# STM32_microcontroller_power.net
KiCad netlist of a schematic drawn in Altium Designer
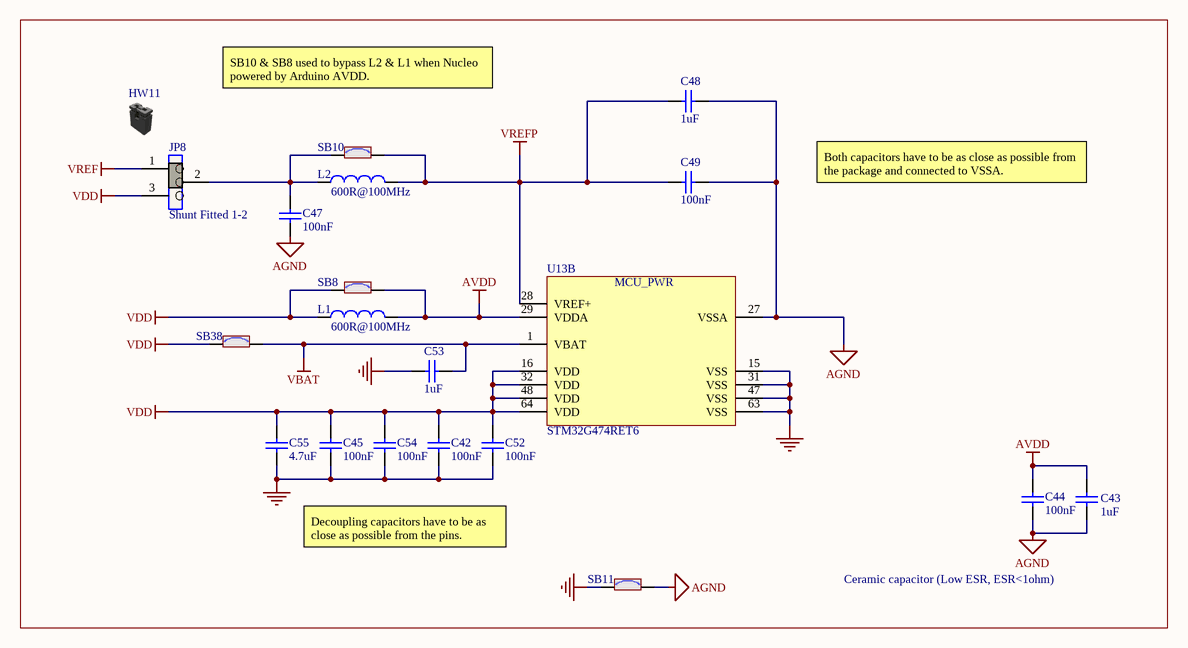
[diagram p0: STM32_microcontroller_power.SchDoc]

(export (version "E")
  (design (tool "Eeschema 10.0.6"))
  (components
    (comp (ref "C42")
      (value "100nF")
      (footprint "C0402")
      (description "Capacitor, MLCC, 100nF, 16V, X7R, 10%, 0402, T=0,5mm")
      (fields
        (field (name "INTERNAL_PART_NUMBER") "MCD-00102")
        (field (name "MANUFACTURER_PART_NUMBER") "CC0402KRX7R7BB104")
        (field (name "PROVIDED_BY") "Subcon")
      )
      (libsource (lib "MCD_PARTS_database") (part "Capacitor"))
    )
    (comp (ref "C43")
      (value "1uF")
      (footprint "C0603")
      (description "Capacitor, MLCC, 1uF, 16V, X5R, 10%, 0603, T=0,8mm")
      (fields
        (field (name "INTERNAL_PART_NUMBER") "MCD-00010")
        (field (name "MANUFACTURER_PART_NUMBER") "CC0603KRX5R7BB105")
        (field (name "PROVIDED_BY") "Subcon")
      )
      (libsource (lib "MCD_PARTS_database") (part "Capacitor"))
    )
    (comp (ref "C44")
      (value "100nF")
      (footprint "C0402")
      (description "Capacitor, MLCC, 100nF, 16V, X7R, 10%, 0402, T=0,5mm")
      (fields
        (field (name "INTERNAL_PART_NUMBER") "MCD-00102")
        (field (name "MANUFACTURER_PART_NUMBER") "CC0402KRX7R7BB104")
        (field (name "PROVIDED_BY") "Subcon")
      )
      (libsource (lib "MCD_PARTS_database") (part "Capacitor"))
    )
    (comp (ref "C45")
      (value "100nF")
      (footprint "C0402")
      (description "Capacitor, MLCC, 100nF, 16V, X7R, 10%, 0402, T=0,5mm")
      (fields
        (field (name "INTERNAL_PART_NUMBER") "MCD-00102")
        (field (name "MANUFACTURER_PART_NUMBER") "CC0402KRX7R7BB104")
        (field (name "PROVIDED_BY") "Subcon")
      )
      (libsource (lib "MCD_PARTS_database") (part "Capacitor"))
    )
    (comp (ref "C47")
      (value "100nF")
      (footprint "C0402")
      (description "Capacitor, MLCC, 100nF, 16V, X7R, 10%, 0402, T=0,5mm")
      (fields
        (field (name "INTERNAL_PART_NUMBER") "MCD-00102")
        (field (name "MANUFACTURER_PART_NUMBER") "CC0402KRX7R7BB104")
        (field (name "PROVIDED_BY") "Subcon")
      )
      (libsource (lib "MCD_PARTS_database") (part "Capacitor"))
    )
    (comp (ref "C48")
      (value "1uF")
      (footprint "C0603")
      (description "Capacitor, MLCC, 1uF, 16V, X5R, 10%, 0603, T=0,8mm")
      (fields
        (field (name "INTERNAL_PART_NUMBER") "MCD-00010")
        (field (name "MANUFACTURER_PART_NUMBER") "CC0603KRX5R7BB105")
        (field (name "PROVIDED_BY") "Subcon")
      )
      (libsource (lib "MCD_PARTS_database") (part "Capacitor"))
    )
    (comp (ref "C49")
      (value "100nF")
      (footprint "C0402")
      (description "Capacitor, MLCC, 100nF, 16V, X7R, 10%, 0402, T=0,5mm")
      (fields
        (field (name "INTERNAL_PART_NUMBER") "MCD-00102")
        (field (name "MANUFACTURER_PART_NUMBER") "CC0402KRX7R7BB104")
        (field (name "PROVIDED_BY") "Subcon")
      )
      (libsource (lib "MCD_PARTS_database") (part "Capacitor"))
    )
    (comp (ref "C52")
      (value "100nF")
      (footprint "C0402")
      (description "Capacitor, MLCC, 100nF, 16V, X7R, 10%, 0402, T=0,5mm")
      (fields
        (field (name "INTERNAL_PART_NUMBER") "MCD-00102")
        (field (name "MANUFACTURER_PART_NUMBER") "CC0402KRX7R7BB104")
        (field (name "PROVIDED_BY") "Subcon")
      )
      (libsource (lib "MCD_PARTS_database") (part "Capacitor"))
    )
    (comp (ref "C53")
      (value "1uF")
      (footprint "C0603")
      (description "Capacitor, MLCC, 1uF, 16V, X5R, 10%, 0603, T=0,8mm")
      (fields
        (field (name "INTERNAL_PART_NUMBER") "MCD-00010")
        (field (name "MANUFACTURER_PART_NUMBER") "CC0603KRX5R7BB105")
        (field (name "PROVIDED_BY") "Subcon")
      )
      (libsource (lib "MCD_PARTS_database") (part "Capacitor"))
    )
    (comp (ref "C54")
      (value "100nF")
      (footprint "C0402")
      (description "Capacitor, MLCC, 100nF, 16V, X7R, 10%, 0402, T=0,5mm")
      (fields
        (field (name "INTERNAL_PART_NUMBER") "MCD-00102")
        (field (name "MANUFACTURER_PART_NUMBER") "CC0402KRX7R7BB104")
        (field (name "PROVIDED_BY") "Subcon")
      )
      (libsource (lib "MCD_PARTS_database") (part "Capacitor"))
    )
    (comp (ref "C55")
      (value "4.7uF")
      (footprint "C0603")
      (description "Capacitor, MLCC, 4.7uF, 16V, X5R, 10%, 0603, T=0.8mm")
      (fields
        (field (name "INTERNAL_PART_NUMBER") "MCD-00009")
        (field (name "MANUFACTURER_PART_NUMBER") "CC0603KRX5R7BB475")
        (field (name "PROVIDED_BY") "subcon")
      )
      (libsource (lib "MCD_PARTS_database") (part "Capacitor"))
    )
    (comp (ref "HW11")
      (value "~")
      (description "SHUNT 2.54mm BLACK")
      (fields
        (field (name "INTERNAL_PART_NUMBER") "MCD-00043")
        (field (name "MANUFACTURER_PART_NUMBER") "SNT-100-BK-G")
        (field (name "PROVIDED_BY") "Subcon")
      )
      (libsource (lib "MCD_PARTS_database") (part "Shunt Black 2.54mm"))
    )
    (comp (ref "JP8")
      (value "Shunt Fitted 1-2")
      (footprint "CON_SAMTEC_TSW-103-07-F-S")
      (description "Header, 3x1, 2,54mm, VR, TH, Height 5.84mm/2.54mm - Shunt Fitted 1-2 by default")
      (fields
        (field (name "INTERNAL_PART_NUMBER") "MCD-00684")
        (field (name "MANUFACTURER_PART_NUMBER") "TSW-103-07-F-S")
        (field (name "PROVIDED_BY") "SUBCO")
      )
      (libsource (lib "MCD_PARTS_database") (part "Jumper_Header 3x1 Fitted 1-2"))
    )
    (comp (ref "L1")
      (value "600R@100MHz")
      (footprint "L0603")
      (description "SMD Chip ferrite bead, 600R@100MHz +/-25%, 350mA, 500mohm DC, 0603, T=0.8mm")
      (fields
        (field (name "INTERNAL_PART_NUMBER") "MCD-00047")
        (field (name "MANUFACTURER_PART_NUMBER") "FCM1608KF-601T03")
        (field (name "PROVIDED_BY") "SUBCO")
      )
      (libsource (lib "MCD_PARTS_database") (part "BEAD"))
    )
    (comp (ref "L2")
      (value "600R@100MHz")
      (footprint "L0603")
      (description "SMD Chip ferrite bead, 600R@100MHz +/-25%, 350mA, 500mohm DC, 0603, T=0.8mm")
      (fields
        (field (name "INTERNAL_PART_NUMBER") "MCD-00047")
        (field (name "MANUFACTURER_PART_NUMBER") "FCM1608KF-601T03")
        (field (name "PROVIDED_BY") "SUBCO")
      )
      (libsource (lib "MCD_PARTS_database") (part "BEAD"))
    )
    (comp (ref "SB8")
      (value "~")
      (footprint "SOLDER-BRIDGE_R0603-0R")
      (description "Solder Bridge ON")
      (fields
        (field (name "INTERNAL_PART_NUMBER") "MCD-00071")
        (field (name "MANUFACTURER_PART_NUMBER") "RC0603JR-070RL")
        (field (name "PROVIDED_BY") "SUBCO")
      )
      (libsource (lib "MCD_PARTS_database") (part "SB_ON"))
    )
    (comp (ref "SB10")
      (value "~")
      (footprint "SOLDER-BRIDGE_R0603-0R")
      (description "Solder Bridge ON")
      (fields
        (field (name "INTERNAL_PART_NUMBER") "MCD-00071")
        (field (name "MANUFACTURER_PART_NUMBER") "RC0603JR-070RL")
        (field (name "PROVIDED_BY") "SUBCO")
      )
      (libsource (lib "MCD_PARTS_database") (part "SB_ON"))
    )
    (comp (ref "SB11")
      (value "~")
      (footprint "SOLDER-BRIDGE_R0603-0R")
      (description "Solder Bridge ON")
      (fields
        (field (name "INTERNAL_PART_NUMBER") "MCD-00071")
        (field (name "MANUFACTURER_PART_NUMBER") "RC0603JR-070RL")
        (field (name "PROVIDED_BY") "SUBCO")
      )
      (libsource (lib "MCD_PARTS_database") (part "SB_ON"))
    )
    (comp (ref "SB38")
      (value "~")
      (footprint "SOLDER-BRIDGE_R0603-0R")
      (description "Solder Bridge ON")
      (fields
        (field (name "INTERNAL_PART_NUMBER") "MCD-00071")
        (field (name "MANUFACTURER_PART_NUMBER") "RC0603JR-070RL")
        (field (name "PROVIDED_BY") "SUBCO")
      )
      (libsource (lib "MCD_PARTS_database") (part "SB_ON"))
    )
    (comp (ref "U13")
      (value "STM32G474RET6")
      (footprint "ICC_LQFP64_10X10_P050_SOCKET_YAMAICHI_IC149-064-069-B5_NM")
      (description "STM32G474, LQFP64 package,  3D IC footprint with 2D socket footprint.")
      (fields
        (field (name "INTERNAL_PART_NUMBER") "MCD-01243")
        (field (name "MANUFACTURER") "STMICROELECTRONICS")
        (field (name "PROVIDED_BY") "SUBCO with ST control")
      )
      (libsource (lib "MCD_PARTS_database") (part "STM32G4xx_LQFP64"))
    )
  )
  (nets
    (net (code "1") (name "AGND") (class "Default")
      (node (ref "C43") (pin "1") (pinfunction "1_1") (pintype "passive"))
      (node (ref "C44") (pin "1") (pinfunction "1_1") (pintype "passive"))
      (node (ref "C47") (pin "1") (pinfunction "1_1") (pintype "passive"))
      (node (ref "C48") (pin "2") (pinfunction "2_2") (pintype "passive"))
      (node (ref "C49") (pin "2") (pinfunction "2_2") (pintype "passive"))
      (node (ref "SB11") (pin "2") (pinfunction "2_2") (pintype "passive"))
      (node (ref "U13") (pin "27") (pinfunction "VSSA_27") (pintype "passive"))
    )
    (net (code "2") (name "AVDD") (class "Default")
      (node (ref "C43") (pin "2") (pinfunction "2_2") (pintype "passive"))
      (node (ref "C44") (pin "2") (pinfunction "2_2") (pintype "passive"))
      (node (ref "L1") (pin "2") (pinfunction "2_2") (pintype "passive"))
      (node (ref "SB8") (pin "2") (pinfunction "2_2") (pintype "passive"))
      (node (ref "U13") (pin "29") (pinfunction "VDDA_29") (pintype "passive"))
    )
    (net (code "3") (name "GND") (class "Default")
      (node (ref "C42") (pin "1") (pinfunction "1_1") (pintype "passive"))
      (node (ref "C45") (pin "1") (pinfunction "1_1") (pintype "passive"))
      (node (ref "C52") (pin "1") (pinfunction "1_1") (pintype "passive"))
      (node (ref "C53") (pin "1") (pinfunction "1_1") (pintype "passive"))
      (node (ref "C54") (pin "1") (pinfunction "1_1") (pintype "passive"))
      (node (ref "C55") (pin "1") (pinfunction "1_1") (pintype "passive"))
      (node (ref "SB11") (pin "1") (pinfunction "1_1") (pintype "passive"))
      (node (ref "U13") (pin "15") (pinfunction "VSS_15") (pintype "passive"))
      (node (ref "U13") (pin "31") (pinfunction "VSS_31") (pintype "passive"))
      (node (ref "U13") (pin "47") (pinfunction "VSS_47") (pintype "passive"))
      (node (ref "U13") (pin "63") (pinfunction "VSS_63") (pintype "passive"))
    )
    (net (code "4") (name "Net-(C47-Pad2)") (class "Default")
      (node (ref "C47") (pin "2") (pinfunction "2_2") (pintype "passive"))
      (node (ref "JP8") (pin "2") (pinfunction "2_2") (pintype "passive"))
      (node (ref "L2") (pin "1") (pinfunction "1_1") (pintype "passive"))
      (node (ref "SB10") (pin "1") (pinfunction "1_1") (pintype "passive"))
    )
    (net (code "5") (name "VBAT") (class "Default")
      (node (ref "C53") (pin "2") (pinfunction "2_2") (pintype "passive"))
      (node (ref "SB38") (pin "2") (pinfunction "2_2") (pintype "passive"))
      (node (ref "U13") (pin "1") (pinfunction "VBAT_1") (pintype "passive"))
    )
    (net (code "6") (name "VDD") (class "Default")
      (node (ref "C42") (pin "2") (pinfunction "2_2") (pintype "passive"))
      (node (ref "C45") (pin "2") (pinfunction "2_2") (pintype "passive"))
      (node (ref "C52") (pin "2") (pinfunction "2_2") (pintype "passive"))
      (node (ref "C54") (pin "2") (pinfunction "2_2") (pintype "passive"))
      (node (ref "C55") (pin "2") (pinfunction "2_2") (pintype "passive"))
      (node (ref "JP8") (pin "3") (pinfunction "3_3") (pintype "passive"))
      (node (ref "L1") (pin "1") (pinfunction "1_1") (pintype "passive"))
      (node (ref "SB38") (pin "1") (pinfunction "1_1") (pintype "passive"))
      (node (ref "SB8") (pin "1") (pinfunction "1_1") (pintype "passive"))
      (node (ref "U13") (pin "16") (pinfunction "VDD_16") (pintype "passive"))
      (node (ref "U13") (pin "32") (pinfunction "VDD_32") (pintype "passive"))
      (node (ref "U13") (pin "48") (pinfunction "VDD_48") (pintype "passive"))
      (node (ref "U13") (pin "64") (pinfunction "VDD_64") (pintype "passive"))
    )
    (net (code "7") (name "VREF") (class "Default")
      (node (ref "JP8") (pin "1") (pinfunction "1_1") (pintype "passive"))
    )
    (net (code "8") (name "VREFP") (class "Default")
      (node (ref "C48") (pin "1") (pinfunction "1_1") (pintype "passive"))
      (node (ref "C49") (pin "1") (pinfunction "1_1") (pintype "passive"))
      (node (ref "L2") (pin "2") (pinfunction "2_2") (pintype "passive"))
      (node (ref "SB10") (pin "2") (pinfunction "2_2") (pintype "passive"))
      (node (ref "U13") (pin "28") (pinfunction "VREF+_28") (pintype "passive"))
    )
  )
)
